# eggplant.net
KiCad netlist of a schematic drawn in EAGLE
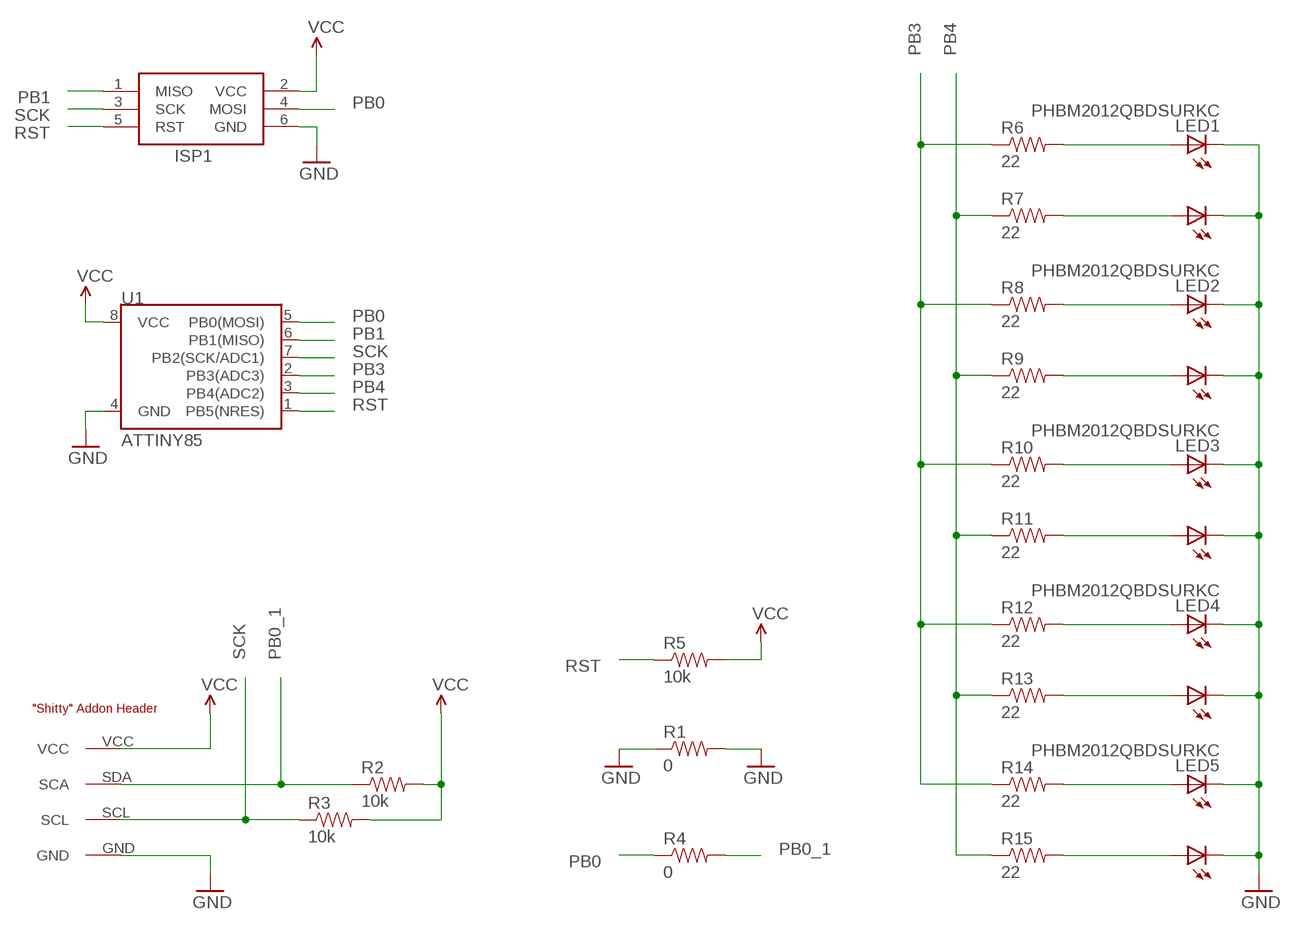
[diagram p0: schematic, sheet 1]

(export (version "E")
  (design (tool "Eeschema 10.0.6"))
  (components
    (comp (ref "ISP1")
      (value "AVRISPPOGO")
      (footprint "eagle-import:AVRISP-POGO")
      (libsource (lib "eagle-import") (part "AVRISPPOGO"))
    )
    (comp (ref "LED1")
      (value "PHBM2012QBDSURKC")
      (footprint "eagle-import:0805-DUALLED")
      (libsource (lib "eagle-import") (part "DUAL_LED0805"))
    )
    (comp (ref "LED2")
      (value "PHBM2012QBDSURKC")
      (footprint "eagle-import:0805-DUALLED")
      (libsource (lib "eagle-import") (part "DUAL_LED0805"))
    )
    (comp (ref "LED3")
      (value "PHBM2012QBDSURKC")
      (footprint "eagle-import:0805-DUALLED")
      (libsource (lib "eagle-import") (part "DUAL_LED0805"))
    )
    (comp (ref "LED4")
      (value "PHBM2012QBDSURKC")
      (footprint "eagle-import:0805-DUALLED")
      (libsource (lib "eagle-import") (part "DUAL_LED0805"))
    )
    (comp (ref "LED5")
      (value "PHBM2012QBDSURKC")
      (footprint "eagle-import:0805-DUALLED")
      (libsource (lib "eagle-import") (part "DUAL_LED0805"))
    )
    (comp (ref "R1")
      (value "0")
      (footprint "eagle-import:0805")
      (libsource (lib "eagle-import") (part "RESISTOR0805-RES"))
    )
    (comp (ref "R2")
      (value "10k")
      (footprint "eagle-import:0603-RES")
      (libsource (lib "eagle-import") (part "RESISTOR0603-RES"))
    )
    (comp (ref "R3")
      (value "10k")
      (footprint "eagle-import:0603-RES")
      (libsource (lib "eagle-import") (part "RESISTOR0603-RES"))
    )
    (comp (ref "R4")
      (value "0")
      (footprint "eagle-import:0805")
      (libsource (lib "eagle-import") (part "RESISTOR0805-RES"))
    )
    (comp (ref "R5")
      (value "10k")
      (footprint "eagle-import:0603-RES")
      (libsource (lib "eagle-import") (part "RESISTOR0603-RES"))
    )
    (comp (ref "R6")
      (value "22")
      (footprint "eagle-import:0603-RES")
      (libsource (lib "eagle-import") (part "RESISTOR0603-RES"))
    )
    (comp (ref "R7")
      (value "22")
      (footprint "eagle-import:0603-RES")
      (libsource (lib "eagle-import") (part "RESISTOR0603-RES"))
    )
    (comp (ref "R8")
      (value "22")
      (footprint "eagle-import:0603-RES")
      (libsource (lib "eagle-import") (part "RESISTOR0603-RES"))
    )
    (comp (ref "R9")
      (value "22")
      (footprint "eagle-import:0603-RES")
      (libsource (lib "eagle-import") (part "RESISTOR0603-RES"))
    )
    (comp (ref "R10")
      (value "22")
      (footprint "eagle-import:0603-RES")
      (libsource (lib "eagle-import") (part "RESISTOR0603-RES"))
    )
    (comp (ref "R11")
      (value "22")
      (footprint "eagle-import:0603-RES")
      (libsource (lib "eagle-import") (part "RESISTOR0603-RES"))
    )
    (comp (ref "R12")
      (value "22")
      (footprint "eagle-import:0603-RES")
      (libsource (lib "eagle-import") (part "RESISTOR0603-RES"))
    )
    (comp (ref "R13")
      (value "22")
      (footprint "eagle-import:0603-RES")
      (libsource (lib "eagle-import") (part "RESISTOR0603-RES"))
    )
    (comp (ref "R14")
      (value "22")
      (footprint "eagle-import:0603-RES")
      (libsource (lib "eagle-import") (part "RESISTOR0603-RES"))
    )
    (comp (ref "R15")
      (value "22")
      (footprint "eagle-import:0603-RES")
      (libsource (lib "eagle-import") (part "RESISTOR0603-RES"))
    )
    (comp (ref "U$1")
      (value "ADDONSC_ADDON_SMD")
      (footprint "eagle-import:SC_ADDON_SMD")
      (libsource (lib "eagle-import") (part "ADDONSC_ADDON_SMD"))
    )
    (comp (ref "U1")
      (value "ATTINY85")
      (footprint "eagle-import:SO08-EIAJ")
      (libsource (lib "eagle-import") (part "ATTINY45"))
    )
  )
  (nets
    (net (code "1") (name "/PB0") (class "Default")
      (node (ref "ISP1") (pin "4") (pinfunction "MOSI_4") (pintype "output"))
      (node (ref "R4") (pin "1") (pinfunction "1_1") (pintype "passive"))
      (node (ref "U1") (pin "5") (pinfunction "PB0(MOSI)_5") (pintype "bidirectional"))
    )
    (net (code "2") (name "/PB0_1") (class "Default")
      (node (ref "R2") (pin "1") (pinfunction "1_1") (pintype "passive"))
      (node (ref "R4") (pin "2") (pinfunction "2_2") (pintype "passive"))
      (node (ref "U$1") (pin "SDA") (pinfunction "SCA_SDA") (pintype "bidirectional"))
    )
    (net (code "3") (name "/PB1") (class "Default")
      (node (ref "ISP1") (pin "1") (pinfunction "MISO_1") (pintype "input"))
      (node (ref "U1") (pin "6") (pinfunction "PB1(MISO)_6") (pintype "bidirectional"))
    )
    (net (code "4") (name "/PB3") (class "Default")
      (node (ref "R10") (pin "1") (pinfunction "1_1") (pintype "passive"))
      (node (ref "R12") (pin "1") (pinfunction "1_1") (pintype "passive"))
      (node (ref "R14") (pin "1") (pinfunction "1_1") (pintype "passive"))
      (node (ref "R6") (pin "1") (pinfunction "1_1") (pintype "passive"))
      (node (ref "R8") (pin "1") (pinfunction "1_1") (pintype "passive"))
      (node (ref "U1") (pin "2") (pinfunction "PB3(ADC3)_2") (pintype "bidirectional"))
    )
    (net (code "5") (name "/PB4") (class "Default")
      (node (ref "R11") (pin "1") (pinfunction "1_1") (pintype "passive"))
      (node (ref "R13") (pin "1") (pinfunction "1_1") (pintype "passive"))
      (node (ref "R15") (pin "1") (pinfunction "1_1") (pintype "passive"))
      (node (ref "R7") (pin "1") (pinfunction "1_1") (pintype "passive"))
      (node (ref "R9") (pin "1") (pinfunction "1_1") (pintype "passive"))
      (node (ref "U1") (pin "3") (pinfunction "PB4(ADC2)_3") (pintype "bidirectional"))
    )
    (net (code "6") (name "/RST") (class "Default")
      (node (ref "ISP1") (pin "5") (pinfunction "RST_5") (pintype "output"))
      (node (ref "R5") (pin "1") (pinfunction "1_1") (pintype "passive"))
      (node (ref "U1") (pin "1") (pinfunction "PB5(NRES)_1") (pintype "bidirectional"))
    )
    (net (code "7") (name "/SCK") (class "Default")
      (node (ref "ISP1") (pin "3") (pinfunction "SCK_3") (pintype "output"))
      (node (ref "R3") (pin "1") (pinfunction "1_1") (pintype "passive"))
      (node (ref "U$1") (pin "SCL") (pinfunction "SCL_SCL") (pintype "bidirectional"))
      (node (ref "U1") (pin "7") (pinfunction "PB2(SCK/ADC1)_7") (pintype "bidirectional"))
    )
    (net (code "8") (name "GND") (class "Default")
      (node (ref "ISP1") (pin "6") (pinfunction "GND_6") (pintype "power_in"))
      (node (ref "LED1") (pin "CB") (pinfunction "C1_CB") (pintype "output"))
      (node (ref "LED1") (pin "CR") (pinfunction "C2_CR") (pintype "output"))
      (node (ref "LED2") (pin "CB") (pinfunction "C1_CB") (pintype "output"))
      (node (ref "LED2") (pin "CR") (pinfunction "C2_CR") (pintype "output"))
      (node (ref "LED3") (pin "CB") (pinfunction "C1_CB") (pintype "output"))
      (node (ref "LED3") (pin "CR") (pinfunction "C2_CR") (pintype "output"))
      (node (ref "LED4") (pin "CB") (pinfunction "C1_CB") (pintype "output"))
      (node (ref "LED4") (pin "CR") (pinfunction "C2_CR") (pintype "output"))
      (node (ref "LED5") (pin "CB") (pinfunction "C1_CB") (pintype "output"))
      (node (ref "LED5") (pin "CR") (pinfunction "C2_CR") (pintype "output"))
      (node (ref "R1") (pin "1") (pinfunction "1_1") (pintype "passive"))
      (node (ref "R1") (pin "2") (pinfunction "2_2") (pintype "passive"))
      (node (ref "U$1") (pin "GND") (pinfunction "GND_GND") (pintype "bidirectional"))
      (node (ref "U1") (pin "4") (pinfunction "GND_4") (pintype "bidirectional"))
    )
    (net (code "9") (name "Net-(LED1-A1)") (class "Default")
      (node (ref "LED1") (pin "AB") (pinfunction "A1_AB") (pintype "input"))
      (node (ref "R6") (pin "2") (pinfunction "2_2") (pintype "passive"))
    )
    (net (code "10") (name "Net-(LED1-A2)") (class "Default")
      (node (ref "LED1") (pin "AR") (pinfunction "A2_AR") (pintype "input"))
      (node (ref "R7") (pin "2") (pinfunction "2_2") (pintype "passive"))
    )
    (net (code "11") (name "Net-(LED2-A1)") (class "Default")
      (node (ref "LED2") (pin "AB") (pinfunction "A1_AB") (pintype "input"))
      (node (ref "R8") (pin "2") (pinfunction "2_2") (pintype "passive"))
    )
    (net (code "12") (name "Net-(LED2-A2)") (class "Default")
      (node (ref "LED2") (pin "AR") (pinfunction "A2_AR") (pintype "input"))
      (node (ref "R9") (pin "2") (pinfunction "2_2") (pintype "passive"))
    )
    (net (code "13") (name "Net-(LED3-A1)") (class "Default")
      (node (ref "LED3") (pin "AB") (pinfunction "A1_AB") (pintype "input"))
      (node (ref "R10") (pin "2") (pinfunction "2_2") (pintype "passive"))
    )
    (net (code "14") (name "Net-(LED3-A2)") (class "Default")
      (node (ref "LED3") (pin "AR") (pinfunction "A2_AR") (pintype "input"))
      (node (ref "R11") (pin "2") (pinfunction "2_2") (pintype "passive"))
    )
    (net (code "15") (name "Net-(LED4-A1)") (class "Default")
      (node (ref "LED4") (pin "AB") (pinfunction "A1_AB") (pintype "input"))
      (node (ref "R12") (pin "2") (pinfunction "2_2") (pintype "passive"))
    )
    (net (code "16") (name "Net-(LED4-A2)") (class "Default")
      (node (ref "LED4") (pin "AR") (pinfunction "A2_AR") (pintype "input"))
      (node (ref "R13") (pin "2") (pinfunction "2_2") (pintype "passive"))
    )
    (net (code "17") (name "Net-(LED5-A1)") (class "Default")
      (node (ref "LED5") (pin "AB") (pinfunction "A1_AB") (pintype "input"))
      (node (ref "R14") (pin "2") (pinfunction "2_2") (pintype "passive"))
    )
    (net (code "18") (name "Net-(LED5-A2)") (class "Default")
      (node (ref "LED5") (pin "AR") (pinfunction "A2_AR") (pintype "input"))
      (node (ref "R15") (pin "2") (pinfunction "2_2") (pintype "passive"))
    )
    (net (code "19") (name "VCC") (class "Default")
      (node (ref "ISP1") (pin "2") (pinfunction "VCC_2") (pintype "power_in"))
      (node (ref "R2") (pin "2") (pinfunction "2_2") (pintype "passive"))
      (node (ref "R3") (pin "2") (pinfunction "2_2") (pintype "passive"))
      (node (ref "R5") (pin "2") (pinfunction "2_2") (pintype "passive"))
      (node (ref "U$1") (pin "VCC") (pinfunction "VCC_VCC") (pintype "bidirectional"))
      (node (ref "U1") (pin "8") (pinfunction "VCC_8") (pintype "bidirectional"))
    )
  )
)
